# FECIW5SIN365UPQ.net
KiCad netlist of a schematic drawn in EAGLE
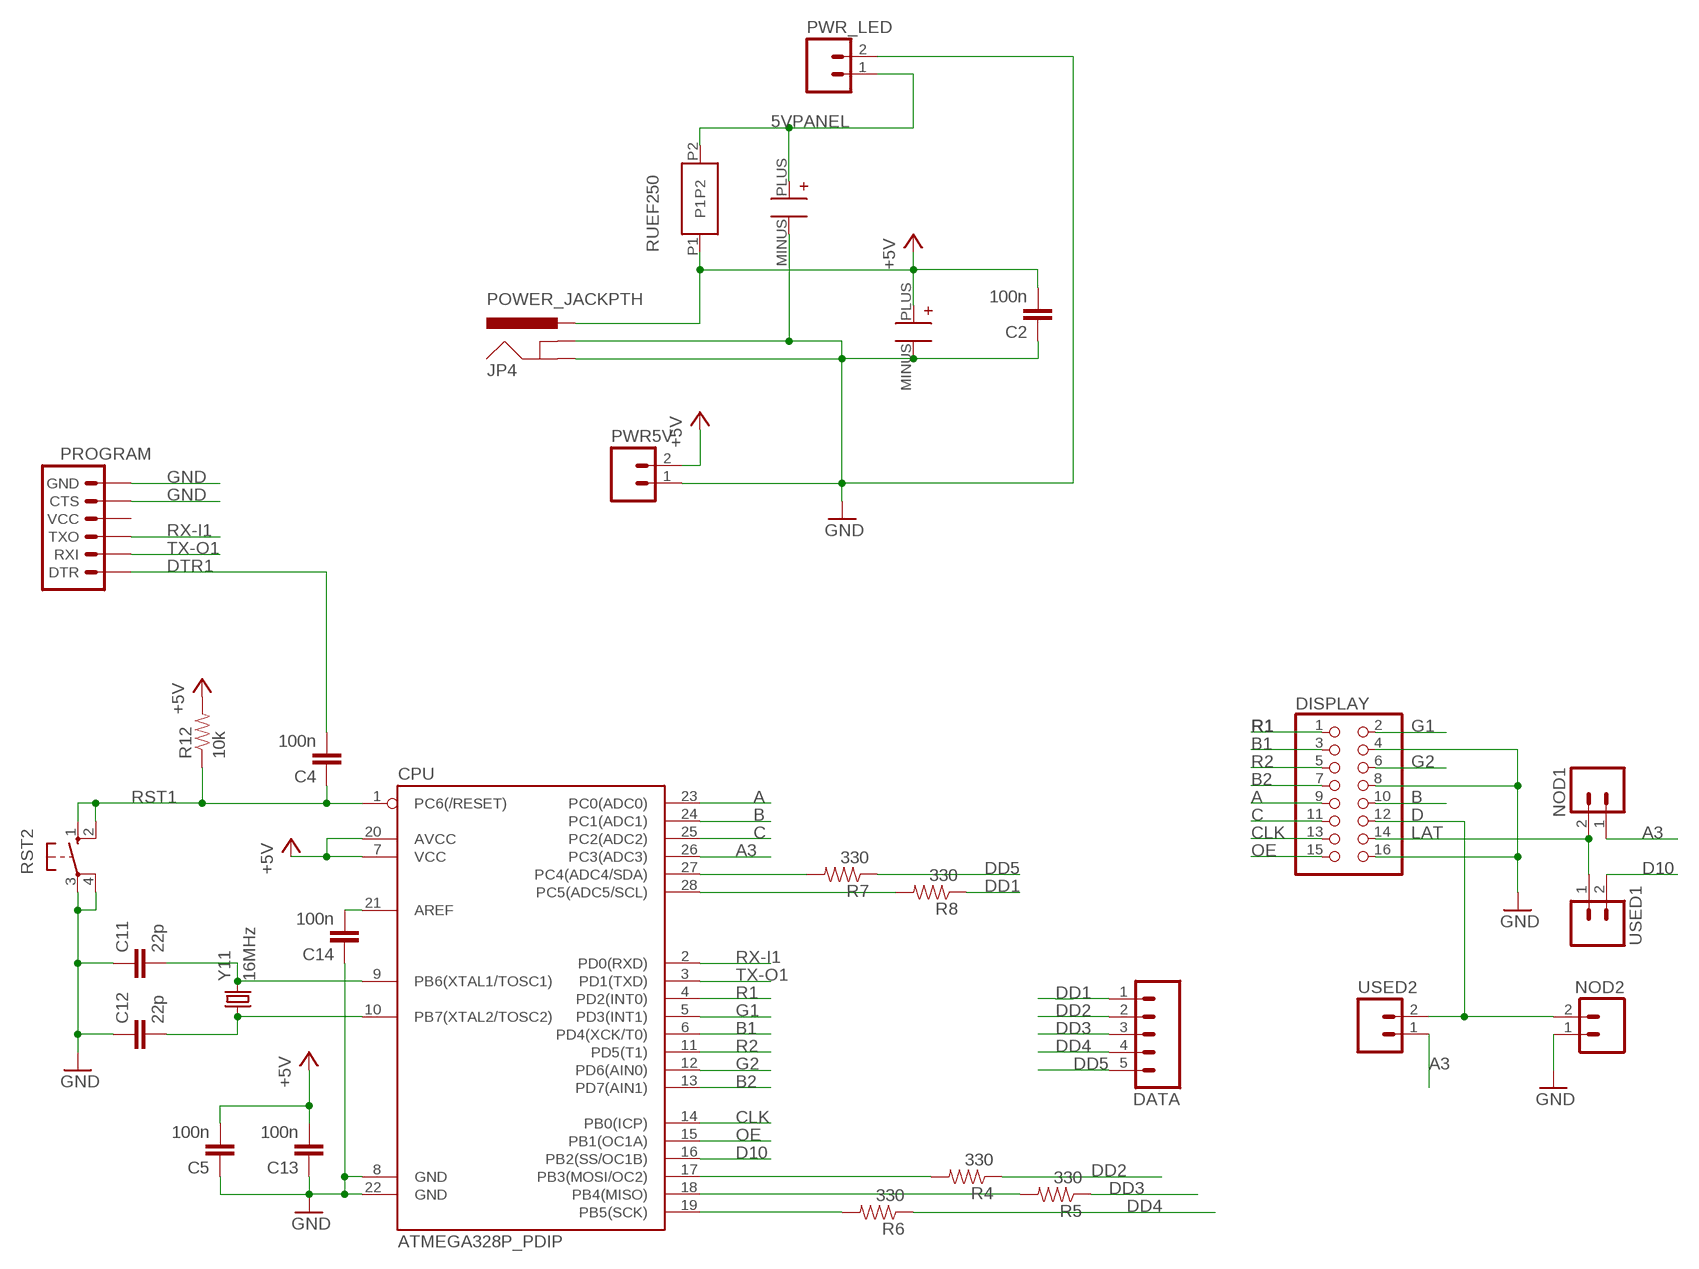
[diagram p0: schematic, sheet 1]

(export (version "E")
  (design (tool "Eeschema 10.0.6"))
  (components
    (comp (ref "C1")
      (value "EEU-FR1C471B")
      (footprint "eagle-import:EEU-FR1C471B")
      (libsource (lib "eagle-import") (part "EEU-FR1C471B"))
    )
    (comp (ref "C2")
      (value "100n")
      (footprint "eagle-import:C025-024X044")
      (libsource (lib "eagle-import") (part "C-EU025-024X044"))
    )
    (comp (ref "C4")
      (value "100n")
      (footprint "eagle-import:C025-024X044")
      (libsource (lib "eagle-import") (part "C-EU025-024X044"))
    )
    (comp (ref "C5")
      (value "100n")
      (footprint "eagle-import:C025-024X044")
      (libsource (lib "eagle-import") (part "C-EU025-024X044"))
    )
    (comp (ref "C7")
      (value "EEU-FR1C471B")
      (footprint "eagle-import:EEU-FR1C471B")
      (libsource (lib "eagle-import") (part "EEU-FR1C471B"))
    )
    (comp (ref "C11")
      (value "22p")
      (footprint "eagle-import:C025-024X044")
      (libsource (lib "eagle-import") (part "C-EU025-024X044"))
    )
    (comp (ref "C12")
      (value "22p")
      (footprint "eagle-import:C025-024X044")
      (libsource (lib "eagle-import") (part "C-EU025-024X044"))
    )
    (comp (ref "C13")
      (value "100n")
      (footprint "eagle-import:C025-024X044")
      (libsource (lib "eagle-import") (part "C-EU025-024X044"))
    )
    (comp (ref "C14")
      (value "100n")
      (footprint "eagle-import:C025-024X044")
      (libsource (lib "eagle-import") (part "C-EU025-024X044"))
    )
    (comp (ref "CPU")
      (value "ATMEGA328P_PDIP")
      (footprint "eagle-import:DIL28-3")
      (libsource (lib "eagle-import") (part "ATMEGA328P_PDIP"))
    )
    (comp (ref "DATA")
      (value "M05PTH")
      (footprint "eagle-import:1X05")
      (libsource (lib "eagle-import") (part "M05PTH"))
    )
    (comp (ref "DISPLAY")
      (value "PINHD-2X8")
      (footprint "eagle-import:2X08")
      (libsource (lib "eagle-import") (part "PINHD-2X8"))
    )
    (comp (ref "JP4")
      (value "POWER_JACKPTH")
      (footprint "eagle-import:POWER_JACK_PTH")
      (libsource (lib "eagle-import") (part "POWER_JACKPTH"))
    )
    (comp (ref "NOD1")
      (value "M02PTH")
      (footprint "eagle-import:1X02")
      (libsource (lib "eagle-import") (part "M02PTH"))
    )
    (comp (ref "NOD2")
      (value "M02PTH")
      (footprint "eagle-import:1X02")
      (libsource (lib "eagle-import") (part "M02PTH"))
    )
    (comp (ref "PROGRAM")
      (value "ARDUINO_SERIAL_PROGRAMPTH")
      (footprint "eagle-import:1X06")
      (libsource (lib "eagle-import") (part "ARDUINO_SERIAL_PROGRAMPTH"))
    )
    (comp (ref "PWR5V")
      (value "M02PTH")
      (footprint "eagle-import:1X02")
      (libsource (lib "eagle-import") (part "M02PTH"))
    )
    (comp (ref "PWR_LED")
      (value "M023.5MM")
      (footprint "eagle-import:SCREWTERMINAL-3.5MM-2")
      (libsource (lib "eagle-import") (part "M023.5MM"))
    )
    (comp (ref "R4")
      (value "330")
      (footprint "eagle-import:AXIAL-0.3")
      (libsource (lib "eagle-import") (part "RESISTORAXIAL-0.3"))
    )
    (comp (ref "R5")
      (value "330")
      (footprint "eagle-import:AXIAL-0.3")
      (libsource (lib "eagle-import") (part "RESISTORAXIAL-0.3"))
    )
    (comp (ref "R6")
      (value "330")
      (footprint "eagle-import:AXIAL-0.3")
      (libsource (lib "eagle-import") (part "RESISTORAXIAL-0.3"))
    )
    (comp (ref "R7")
      (value "330")
      (footprint "eagle-import:AXIAL-0.3")
      (libsource (lib "eagle-import") (part "RESISTORAXIAL-0.3"))
    )
    (comp (ref "R8")
      (value "330")
      (footprint "eagle-import:AXIAL-0.3")
      (libsource (lib "eagle-import") (part "RESISTORAXIAL-0.3"))
    )
    (comp (ref "R12")
      (value "10k")
      (footprint "eagle-import:AXIAL-0.3")
      (libsource (lib "eagle-import") (part "RESISTORAXIAL-0.3"))
    )
    (comp (ref "RST2")
      (value "10-XX")
      (footprint "eagle-import:B3F-10XX")
      (fields (field (name "MPN") "B3F-1000"))
      (libsource (lib "eagle-import") (part "10-XX"))
    )
    (comp (ref "RUEF250")
      (value "RUEF250U")
      (footprint "eagle-import:RUEF250U")
      (libsource (lib "eagle-import") (part "RUEF250U"))
    )
    (comp (ref "USED1")
      (value "M02PTH")
      (footprint "eagle-import:1X02")
      (libsource (lib "eagle-import") (part "M02PTH"))
    )
    (comp (ref "USED2")
      (value "M02PTH")
      (footprint "eagle-import:1X02")
      (libsource (lib "eagle-import") (part "M02PTH"))
    )
    (comp (ref "Y11")
      (value "16MHz")
      (footprint "eagle-import:HC49US")
      (libsource (lib "eagle-import") (part "CRYSTALHC49US"))
    )
  )
  (nets
    (net (code "1") (name "+5V") (class "Default")
      (node (ref "C1") (pin "PLUS") (pinfunction "PLUS_PLUS") (pintype "bidirectional"))
      (node (ref "C13") (pin "2") (pinfunction "2_2") (pintype "passive"))
      (node (ref "C2") (pin "2") (pinfunction "2_2") (pintype "passive"))
      (node (ref "C5") (pin "2") (pinfunction "2_2") (pintype "passive"))
      (node (ref "CPU") (pin "20") (pinfunction "AVCC_20") (pintype "bidirectional"))
      (node (ref "CPU") (pin "7") (pinfunction "VCC_7") (pintype "bidirectional"))
      (node (ref "JP4") (pin "PWR") (pinfunction "PWR_PWR") (pintype "bidirectional"))
      (node (ref "PWR5V") (pin "2") (pinfunction "2_2") (pintype "passive"))
      (node (ref "R12") (pin "P$2") (pinfunction "2_P$2") (pintype "passive"))
      (node (ref "RUEF250") (pin "P1") (pinfunction "P1_P1") (pintype "bidirectional"))
    )
    (net (code "2") (name "/5VPANEL") (class "Default")
      (node (ref "C7") (pin "PLUS") (pinfunction "PLUS_PLUS") (pintype "bidirectional"))
      (node (ref "PWR_LED") (pin "1") (pinfunction "1_1") (pintype "passive"))
      (node (ref "RUEF250") (pin "P2") (pinfunction "P2_P2") (pintype "bidirectional"))
    )
    (net (code "3") (name "/A") (class "Default")
      (node (ref "CPU") (pin "23") (pinfunction "PC0(ADC0)_23") (pintype "bidirectional"))
      (node (ref "DISPLAY") (pin "9") (pinfunction "9_9") (pintype "passive"))
    )
    (net (code "4") (name "/A3") (class "Default")
      (node (ref "CPU") (pin "26") (pinfunction "PC3(ADC3)_26") (pintype "bidirectional"))
      (node (ref "NOD1") (pin "1") (pinfunction "1_1") (pintype "passive"))
      (node (ref "USED2") (pin "1") (pinfunction "1_1") (pintype "passive"))
    )
    (net (code "5") (name "/B") (class "Default")
      (node (ref "CPU") (pin "24") (pinfunction "PC1(ADC1)_24") (pintype "bidirectional"))
      (node (ref "DISPLAY") (pin "10") (pinfunction "10_10") (pintype "passive"))
    )
    (net (code "6") (name "/B1") (class "Default")
      (node (ref "CPU") (pin "6") (pinfunction "PD4(XCK/T0)_6") (pintype "bidirectional"))
      (node (ref "DISPLAY") (pin "3") (pinfunction "3_3") (pintype "passive"))
    )
    (net (code "7") (name "/B2") (class "Default")
      (node (ref "CPU") (pin "13") (pinfunction "PD7(AIN1)_13") (pintype "bidirectional"))
      (node (ref "DISPLAY") (pin "7") (pinfunction "7_7") (pintype "passive"))
    )
    (net (code "8") (name "/C") (class "Default")
      (node (ref "CPU") (pin "25") (pinfunction "PC2(ADC2)_25") (pintype "bidirectional"))
      (node (ref "DISPLAY") (pin "11") (pinfunction "11_11") (pintype "passive"))
    )
    (net (code "9") (name "/CLK") (class "Default")
      (node (ref "CPU") (pin "14") (pinfunction "PB0(ICP)_14") (pintype "bidirectional"))
      (node (ref "DISPLAY") (pin "13") (pinfunction "13_13") (pintype "passive"))
    )
    (net (code "10") (name "/D") (class "Default")
      (node (ref "DISPLAY") (pin "12") (pinfunction "12_12") (pintype "passive"))
      (node (ref "NOD2") (pin "2") (pinfunction "2_2") (pintype "passive"))
      (node (ref "USED2") (pin "2") (pinfunction "2_2") (pintype "passive"))
    )
    (net (code "11") (name "/D10") (class "Default")
      (node (ref "CPU") (pin "16") (pinfunction "PB2(SS/OC1B)_16") (pintype "bidirectional"))
      (node (ref "USED1") (pin "2") (pinfunction "2_2") (pintype "passive"))
    )
    (net (code "12") (name "/DD1") (class "Default")
      (node (ref "DATA") (pin "1") (pinfunction "1_1") (pintype "passive"))
      (node (ref "R8") (pin "P$1") (pinfunction "1_P$1") (pintype "passive"))
    )
    (net (code "13") (name "/DD2") (class "Default")
      (node (ref "DATA") (pin "2") (pinfunction "2_2") (pintype "passive"))
      (node (ref "R4") (pin "P$1") (pinfunction "1_P$1") (pintype "passive"))
    )
    (net (code "14") (name "/DD3") (class "Default")
      (node (ref "DATA") (pin "3") (pinfunction "3_3") (pintype "passive"))
      (node (ref "R5") (pin "P$1") (pinfunction "1_P$1") (pintype "passive"))
    )
    (net (code "15") (name "/DD4") (class "Default")
      (node (ref "DATA") (pin "4") (pinfunction "4_4") (pintype "passive"))
      (node (ref "R6") (pin "P$1") (pinfunction "1_P$1") (pintype "passive"))
    )
    (net (code "16") (name "/DD5") (class "Default")
      (node (ref "DATA") (pin "5") (pinfunction "5_5") (pintype "passive"))
      (node (ref "R7") (pin "P$1") (pinfunction "1_P$1") (pintype "passive"))
    )
    (net (code "17") (name "/DTR1") (class "Default")
      (node (ref "C4") (pin "2") (pinfunction "2_2") (pintype "passive"))
      (node (ref "PROGRAM") (pin "1") (pinfunction "DTR_1") (pintype "passive"))
    )
    (net (code "18") (name "/G1") (class "Default")
      (node (ref "CPU") (pin "5") (pinfunction "PD3(INT1)_5") (pintype "bidirectional"))
      (node (ref "DISPLAY") (pin "2") (pinfunction "2_2") (pintype "passive"))
    )
    (net (code "19") (name "/G2") (class "Default")
      (node (ref "CPU") (pin "12") (pinfunction "PD6(AIN0)_12") (pintype "bidirectional"))
      (node (ref "DISPLAY") (pin "6") (pinfunction "6_6") (pintype "passive"))
    )
    (net (code "20") (name "/LAT") (class "Default")
      (node (ref "DISPLAY") (pin "14") (pinfunction "14_14") (pintype "passive"))
      (node (ref "NOD1") (pin "2") (pinfunction "2_2") (pintype "passive"))
      (node (ref "USED1") (pin "1") (pinfunction "1_1") (pintype "passive"))
    )
    (net (code "21") (name "/OE") (class "Default")
      (node (ref "CPU") (pin "15") (pinfunction "PB1(OC1A)_15") (pintype "bidirectional"))
      (node (ref "DISPLAY") (pin "15") (pinfunction "15_15") (pintype "passive"))
    )
    (net (code "22") (name "/R1") (class "Default")
      (node (ref "CPU") (pin "4") (pinfunction "PD2(INT0)_4") (pintype "bidirectional"))
      (node (ref "DISPLAY") (pin "1") (pinfunction "1_1") (pintype "passive"))
    )
    (net (code "23") (name "/R2") (class "Default")
      (node (ref "CPU") (pin "11") (pinfunction "PD5(T1)_11") (pintype "bidirectional"))
      (node (ref "DISPLAY") (pin "5") (pinfunction "5_5") (pintype "passive"))
    )
    (net (code "24") (name "/RST1") (class "Default")
      (node (ref "C4") (pin "1") (pinfunction "1_1") (pintype "passive"))
      (node (ref "CPU") (pin "1") (pinfunction "PC6(/RESET)_1") (pintype "bidirectional"))
      (node (ref "R12") (pin "P$1") (pinfunction "1_P$1") (pintype "passive"))
      (node (ref "RST2") (pin "1") (pinfunction "S_1") (pintype "passive"))
      (node (ref "RST2") (pin "2") (pinfunction "S1_2") (pintype "passive"))
    )
    (net (code "25") (name "/RX-I1") (class "Default")
      (node (ref "CPU") (pin "2") (pinfunction "PD0(RXD)_2") (pintype "bidirectional"))
      (node (ref "PROGRAM") (pin "3") (pinfunction "TXO_3") (pintype "passive"))
    )
    (net (code "26") (name "/TX-O1") (class "Default")
      (node (ref "CPU") (pin "3") (pinfunction "PD1(TXD)_3") (pintype "bidirectional"))
      (node (ref "PROGRAM") (pin "2") (pinfunction "RXI_2") (pintype "passive"))
    )
    (net (code "27") (name "GND") (class "Default")
      (node (ref "C1") (pin "MINUS") (pinfunction "MINUS_MINUS") (pintype "bidirectional"))
      (node (ref "C11") (pin "1") (pinfunction "1_1") (pintype "passive"))
      (node (ref "C12") (pin "1") (pinfunction "1_1") (pintype "passive"))
      (node (ref "C13") (pin "1") (pinfunction "1_1") (pintype "passive"))
      (node (ref "C14") (pin "1") (pinfunction "1_1") (pintype "passive"))
      (node (ref "C2") (pin "1") (pinfunction "1_1") (pintype "passive"))
      (node (ref "C5") (pin "1") (pinfunction "1_1") (pintype "passive"))
      (node (ref "C7") (pin "MINUS") (pinfunction "MINUS_MINUS") (pintype "bidirectional"))
      (node (ref "CPU") (pin "22") (pinfunction "GND_22") (pintype "bidirectional"))
      (node (ref "CPU") (pin "8") (pinfunction "GND_8") (pintype "bidirectional"))
      (node (ref "DISPLAY") (pin "16") (pinfunction "16_16") (pintype "passive"))
      (node (ref "DISPLAY") (pin "4") (pinfunction "4_4") (pintype "passive"))
      (node (ref "DISPLAY") (pin "8") (pinfunction "8_8") (pintype "passive"))
      (node (ref "JP4") (pin "GND") (pinfunction "GND_GND") (pintype "bidirectional"))
      (node (ref "JP4") (pin "GNDBREAK") (pinfunction "GNDBREAK_GNDBREAK") (pintype "bidirectional"))
      (node (ref "NOD2") (pin "1") (pinfunction "1_1") (pintype "passive"))
      (node (ref "PROGRAM") (pin "5") (pinfunction "CTS_5") (pintype "passive"))
      (node (ref "PROGRAM") (pin "6") (pinfunction "GND_6") (pintype "passive"))
      (node (ref "PWR5V") (pin "1") (pinfunction "1_1") (pintype "passive"))
      (node (ref "PWR_LED") (pin "2") (pinfunction "2_2") (pintype "passive"))
      (node (ref "RST2") (pin "3") (pinfunction "P_3") (pintype "passive"))
      (node (ref "RST2") (pin "4") (pinfunction "P1_4") (pintype "passive"))
    )
    (net (code "28") (name "Net-(CPU-AREF)") (class "Default")
      (node (ref "C14") (pin "2") (pinfunction "2_2") (pintype "passive"))
      (node (ref "CPU") (pin "21") (pinfunction "AREF_21") (pintype "bidirectional"))
    )
    (net (code "29") (name "Net-(CPU-PB3(MOSI{slash}OC2))") (class "Default")
      (node (ref "CPU") (pin "17") (pinfunction "PB3(MOSI/OC2)_17") (pintype "bidirectional"))
      (node (ref "R4") (pin "P$2") (pinfunction "2_P$2") (pintype "passive"))
    )
    (net (code "30") (name "Net-(CPU-PB4(MISO))") (class "Default")
      (node (ref "CPU") (pin "18") (pinfunction "PB4(MISO)_18") (pintype "bidirectional"))
      (node (ref "R5") (pin "P$2") (pinfunction "2_P$2") (pintype "passive"))
    )
    (net (code "31") (name "Net-(CPU-PB5(SCK))") (class "Default")
      (node (ref "CPU") (pin "19") (pinfunction "PB5(SCK)_19") (pintype "bidirectional"))
      (node (ref "R6") (pin "P$2") (pinfunction "2_P$2") (pintype "passive"))
    )
    (net (code "32") (name "Net-(CPU-PB6(XTAL1{slash}TOSC1))") (class "Default")
      (node (ref "C11") (pin "2") (pinfunction "2_2") (pintype "passive"))
      (node (ref "CPU") (pin "9") (pinfunction "PB6(XTAL1/TOSC1)_9") (pintype "bidirectional"))
      (node (ref "Y11") (pin "2") (pinfunction "2_2") (pintype "passive"))
    )
    (net (code "33") (name "Net-(CPU-PB7(XTAL2{slash}TOSC2))") (class "Default")
      (node (ref "C12") (pin "2") (pinfunction "2_2") (pintype "passive"))
      (node (ref "CPU") (pin "10") (pinfunction "PB7(XTAL2/TOSC2)_10") (pintype "bidirectional"))
      (node (ref "Y11") (pin "1") (pinfunction "1_1") (pintype "passive"))
    )
    (net (code "34") (name "Net-(CPU-PC4(ADC4{slash}SDA))") (class "Default")
      (node (ref "CPU") (pin "27") (pinfunction "PC4(ADC4/SDA)_27") (pintype "bidirectional"))
      (node (ref "R7") (pin "P$2") (pinfunction "2_P$2") (pintype "passive"))
    )
    (net (code "35") (name "Net-(CPU-PC5(ADC5{slash}SCL))") (class "Default")
      (node (ref "CPU") (pin "28") (pinfunction "PC5(ADC5/SCL)_28") (pintype "bidirectional"))
      (node (ref "R8") (pin "P$2") (pinfunction "2_P$2") (pintype "passive"))
    )
    (net (code "36") (name "unconnected-(PROGRAM-VCC-Pad4)") (class "Default")
      (node (ref "PROGRAM") (pin "4") (pinfunction "VCC_4") (pintype "passive"))
    )
  )
)
